# PSU_LM1084_ADJ.net
KiCad netlist of a schematic drawn in Altium Designer
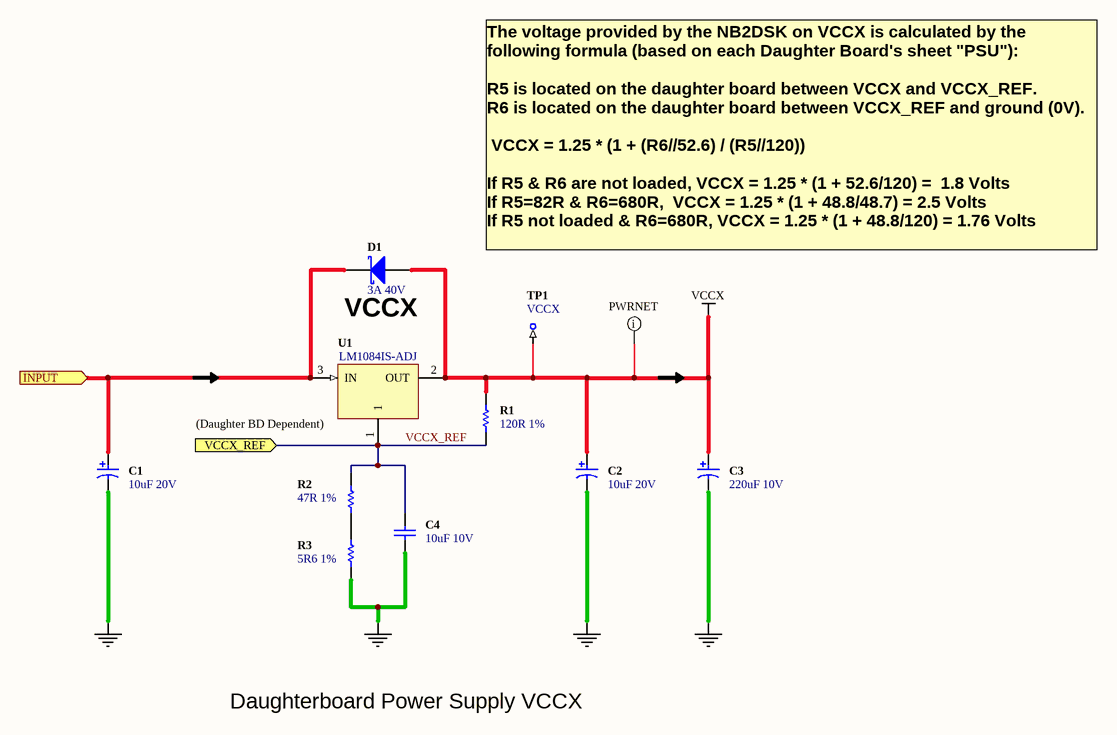
[diagram p0: PSU_LM1084_ADJ.SchDoc]

(export (version "E")
  (design (tool "Eeschema 10.0.6"))
  (components
    (comp (ref "C1")
      (value "10uF 20V")
      (footprint "CAPC3528-STAR")
      (description "Capacitor, Tantalum, 10uF 10% 20V MCCT-B (3528)")
      (fields (field (name "TOLERANCE") "10 %"))
      (libsource (lib "altium-import") (part "root_0_CAP-P_"))
    )
    (comp (ref "C2")
      (value "10uF 20V")
      (footprint "CAPC3528-STAR")
      (description "Capacitor, Tantalum, 10uF 10% 20V MCCT-B (3528)")
      (fields (field (name "TOLERANCE") "10 %"))
      (libsource (lib "altium-import") (part "root_0_CAP-P_"))
    )
    (comp (ref "C3")
      (value "220uF 10V")
      (footprint "CAPC7343-STAR")
      (description "Capacitor, Tantalum, 220uF 10% 10V MCCT-D (7343-31)")
      (fields (field (name "TOLERANCE") "10 %"))
      (libsource (lib "altium-import") (part "root_0_CAP-P_"))
    )
    (comp (ref "C4")
      (value "10uF 10V")
      (footprint "CAPC2012-STAR")
      (description "Capacitor, Ceramic, 10uF 10% 10V 0805 (2012) X5R")
      (fields (field (name "TOLERANCE") "10 %"))
      (libsource (lib "altium-import") (part "root_2_CAP-NP_"))
    )
    (comp (ref "D1")
      (value "3A 40V")
      (footprint "DIOM5027")
      (description "Schottky Diode, 3A 40V")
      (libsource (lib "altium-import") (part "root_2_DIO-SCHOTTKY-1S_"))
    )
    (comp (ref "R1")
      (value "120R 1%")
      (footprint "RESC1005-STAR")
      (description "Resistor, 120R 1% 0402 (1005)")
      (fields (field (name "TOLERANCE") "1 %"))
      (libsource (lib "altium-import") (part "root_0_RES_"))
    )
    (comp (ref "R2")
      (value "47R 1%")
      (footprint "RESC1005-STAR")
      (description "Resistor, 47R 1% 0402 (1005)")
      (fields (field (name "TOLERANCE") "1 %"))
      (libsource (lib "altium-import") (part "root_0_RES_"))
    )
    (comp (ref "R3")
      (value "5R6 1%")
      (footprint "RESC1005-STAR")
      (description "Resistor, 5R6 1% 0402 (1005)")
      (fields (field (name "TOLERANCE") "1 %"))
      (libsource (lib "altium-import") (part "root_0_RES_"))
    )
    (comp (ref "TP1")
      (value "VCCX")
      (footprint "TestPin")
      (description "Test Point, PCB Mount with Silkscreen Box")
      (libsource (lib "AltiumDesignLibrary") (part "TestPin"))
    )
    (comp (ref "U1")
      (value "LM1084IS-ADJ")
      (footprint "TO254P1435-4")
      (description "LM1084IS-ADJ, 5A Low Dropout Positive Regulators")
      (libsource (lib "altium-import") (part "root_0_VRG-ADJ-3_"))
    )
  )
  (nets
    (net (code "1") (name "/INPUT") (class "Default")
      (node (ref "C1") (pin "1") (pinfunction "1_1") (pintype "passive"))
      (node (ref "D1") (pin "2") (pinfunction "K_2") (pintype "passive"))
      (node (ref "U1") (pin "3") (pinfunction "IN_3") (pintype "input"))
    )
    (net (code "2") (name "/VCCX_REF") (class "Default")
      (node (ref "C4") (pin "2") (pinfunction "2_2") (pintype "passive"))
      (node (ref "R1") (pin "2") (pinfunction "2_2") (pintype "passive"))
      (node (ref "R2") (pin "1") (pinfunction "1_1") (pintype "passive"))
      (node (ref "U1") (pin "1") (pinfunction "1_1") (pintype "passive"))
    )
    (net (code "3") (name "GND") (class "Default")
      (node (ref "C1") (pin "2") (pinfunction "2_2") (pintype "passive"))
      (node (ref "C2") (pin "2") (pinfunction "2_2") (pintype "passive"))
      (node (ref "C3") (pin "2") (pinfunction "2_2") (pintype "passive"))
      (node (ref "C4") (pin "1") (pinfunction "1_1") (pintype "passive"))
      (node (ref "R3") (pin "2") (pinfunction "2_2") (pintype "passive"))
    )
    (net (code "4") (name "Net-(R2-Pad2)") (class "Default")
      (node (ref "R2") (pin "2") (pinfunction "2_2") (pintype "passive"))
      (node (ref "R3") (pin "1") (pinfunction "1_1") (pintype "passive"))
    )
    (net (code "5") (name "VCCX") (class "Default")
      (node (ref "C2") (pin "1") (pinfunction "1_1") (pintype "passive"))
      (node (ref "C3") (pin "1") (pinfunction "1_1") (pintype "passive"))
      (node (ref "D1") (pin "1") (pinfunction "A_1") (pintype "passive"))
      (node (ref "R1") (pin "1") (pinfunction "1_1") (pintype "passive"))
      (node (ref "TP1") (pin "1") (pinfunction "1_1") (pintype "input"))
      (node (ref "U1") (pin "2") (pinfunction "OUT_2") (pintype "power_in"))
      (node (ref "U1") (pin "4") (pinfunction "HeatSink_4") (pintype "power_in"))
    )
  )
)
